# d150_in8_rev_a.net
KiCad netlist of a schematic drawn in EAGLE
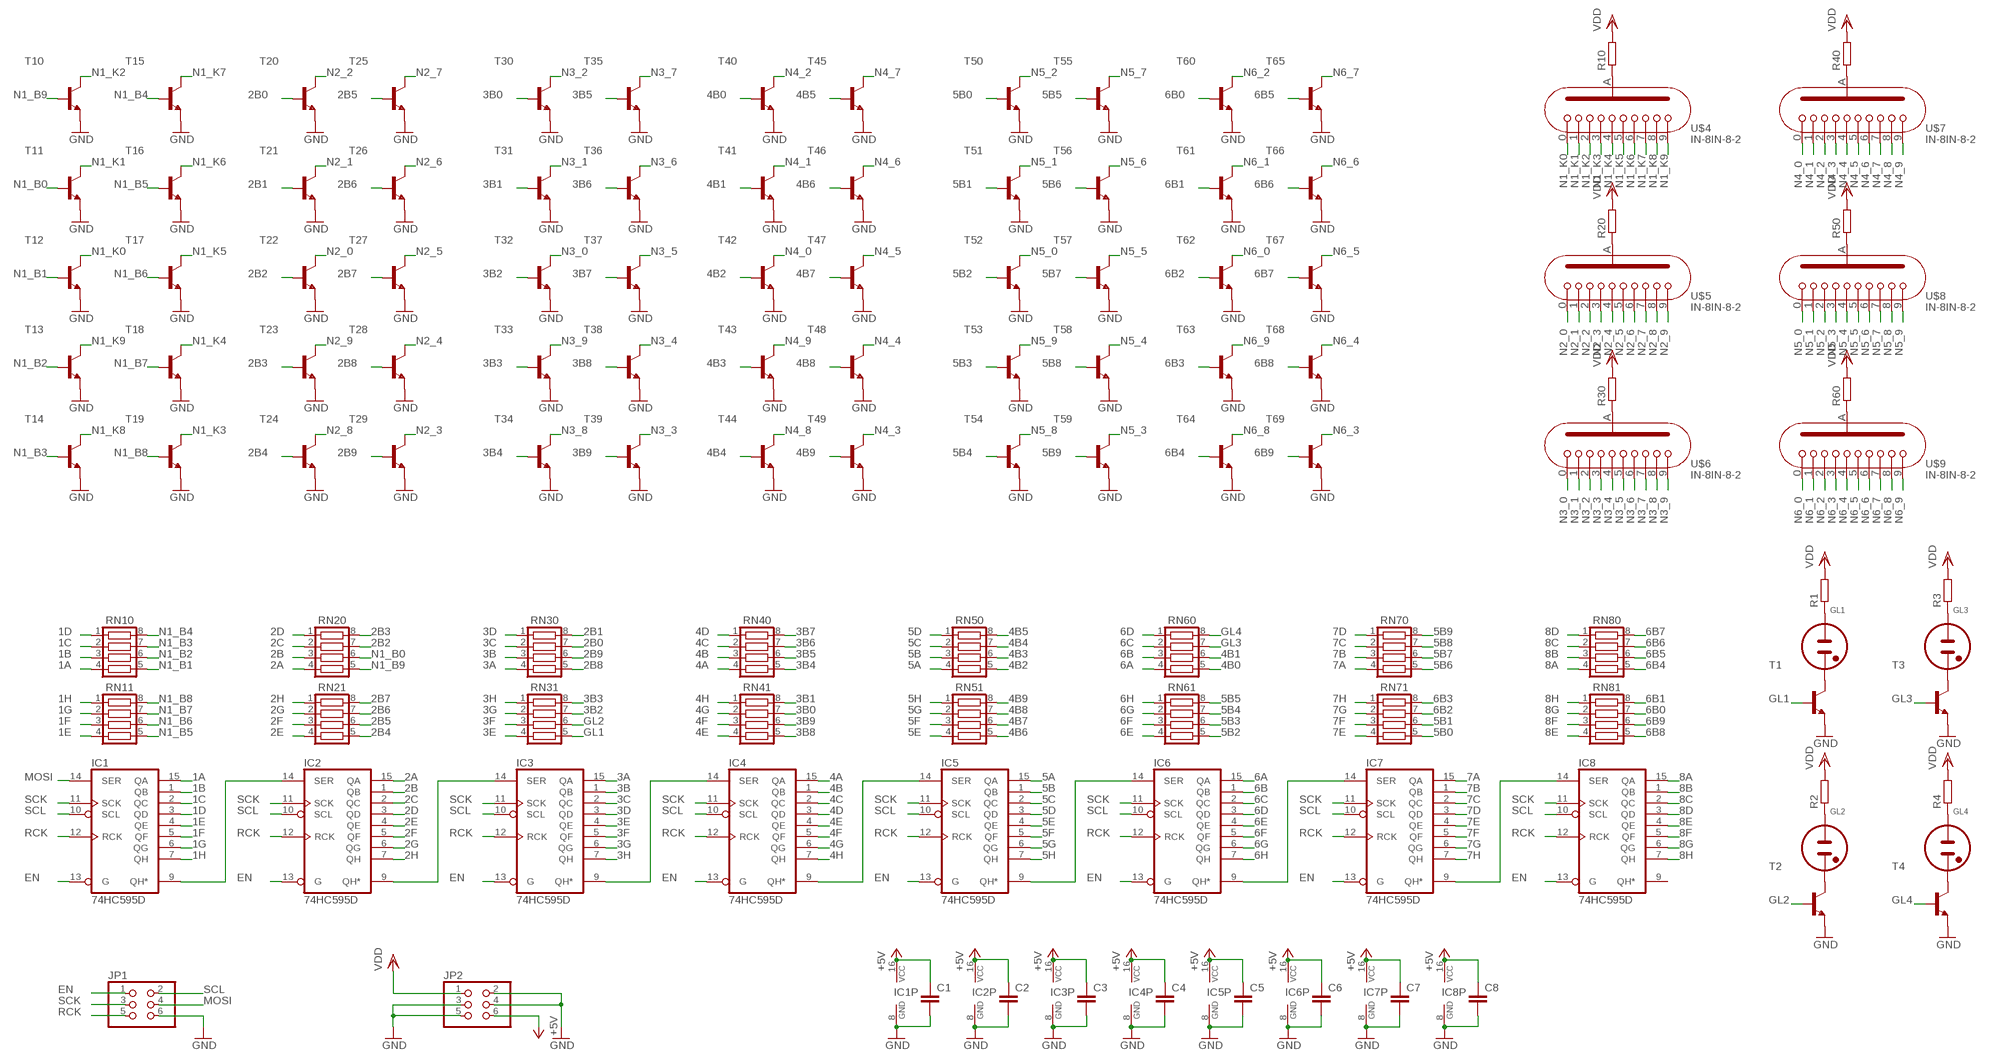
[diagram p0: schematic, sheet 1]

(export (version "E")
  (design (tool "Eeschema 10.0.6"))
  (components
    (comp (ref "C1")
      (value "C-EUC0603")
      (footprint "eagle-import:C0603")
      (libsource (lib "eagle-import") (part "C-EUC0603"))
    )
    (comp (ref "C2")
      (value "C-EUC0603")
      (footprint "eagle-import:C0603")
      (libsource (lib "eagle-import") (part "C-EUC0603"))
    )
    (comp (ref "C3")
      (value "C-EUC0603")
      (footprint "eagle-import:C0603")
      (libsource (lib "eagle-import") (part "C-EUC0603"))
    )
    (comp (ref "C4")
      (value "C-EUC0603")
      (footprint "eagle-import:C0603")
      (libsource (lib "eagle-import") (part "C-EUC0603"))
    )
    (comp (ref "C5")
      (value "C-EUC0603")
      (footprint "eagle-import:C0603")
      (libsource (lib "eagle-import") (part "C-EUC0603"))
    )
    (comp (ref "C6")
      (value "C-EUC0603")
      (footprint "eagle-import:C0603")
      (libsource (lib "eagle-import") (part "C-EUC0603"))
    )
    (comp (ref "C7")
      (value "C-EUC0603")
      (footprint "eagle-import:C0603")
      (libsource (lib "eagle-import") (part "C-EUC0603"))
    )
    (comp (ref "C8")
      (value "C-EUC0603")
      (footprint "eagle-import:C0603")
      (libsource (lib "eagle-import") (part "C-EUC0603"))
    )
    (comp (ref "GL1")
      (value "NE2-NEON-BULB-DRILL")
      (footprint "eagle-import:NE2-NEON-BULB-DRILL")
      (libsource (lib "eagle-import") (part "NE2-NEON-BULB-DRILL"))
    )
    (comp (ref "GL2")
      (value "NE2-NEON-BULB-DRILL")
      (footprint "eagle-import:NE2-NEON-BULB-DRILL")
      (libsource (lib "eagle-import") (part "NE2-NEON-BULB-DRILL"))
    )
    (comp (ref "GL3")
      (value "NE2-NEON-BULB-DRILL")
      (footprint "eagle-import:NE2-NEON-BULB-DRILL")
      (libsource (lib "eagle-import") (part "NE2-NEON-BULB-DRILL"))
    )
    (comp (ref "GL4")
      (value "NE2-NEON-BULB-DRILL")
      (footprint "eagle-import:NE2-NEON-BULB-DRILL")
      (libsource (lib "eagle-import") (part "NE2-NEON-BULB-DRILL"))
    )
    (comp (ref "IC1")
      (value "74HC595D")
      (footprint "eagle-import:SO16")
      (libsource (lib "eagle-import") (part "74595DHC"))
    )
    (comp (ref "IC2")
      (value "74HC595D")
      (footprint "eagle-import:SO16")
      (libsource (lib "eagle-import") (part "74595DHC"))
    )
    (comp (ref "IC3")
      (value "74HC595D")
      (footprint "eagle-import:SO16")
      (libsource (lib "eagle-import") (part "74595DHC"))
    )
    (comp (ref "IC4")
      (value "74HC595D")
      (footprint "eagle-import:SO16")
      (libsource (lib "eagle-import") (part "74595DHC"))
    )
    (comp (ref "IC5")
      (value "74HC595D")
      (footprint "eagle-import:SO16")
      (libsource (lib "eagle-import") (part "74595DHC"))
    )
    (comp (ref "IC6")
      (value "74HC595D")
      (footprint "eagle-import:SO16")
      (libsource (lib "eagle-import") (part "74595DHC"))
    )
    (comp (ref "IC7")
      (value "74HC595D")
      (footprint "eagle-import:SO16")
      (libsource (lib "eagle-import") (part "74595DHC"))
    )
    (comp (ref "IC8")
      (value "74HC595D")
      (footprint "eagle-import:SO16")
      (libsource (lib "eagle-import") (part "74595DHC"))
    )
    (comp (ref "JP1")
      (value "PINHD-2X3_2.54-SMD")
      (footprint "eagle-import:2X03SMD")
      (libsource (lib "eagle-import") (part "PINHD-2X3_2.54-SMD"))
    )
    (comp (ref "JP2")
      (value "PINHD-2X3_2.54-SMD")
      (footprint "eagle-import:2X03SMD")
      (libsource (lib "eagle-import") (part "PINHD-2X3_2.54-SMD"))
    )
    (comp (ref "R1")
      (value "R-EU_R0603")
      (footprint "eagle-import:R0603")
      (libsource (lib "eagle-import") (part "R-EU_R0603"))
    )
    (comp (ref "R2")
      (value "R-EU_R0603")
      (footprint "eagle-import:R0603")
      (libsource (lib "eagle-import") (part "R-EU_R0603"))
    )
    (comp (ref "R3")
      (value "R-EU_R0603")
      (footprint "eagle-import:R0603")
      (libsource (lib "eagle-import") (part "R-EU_R0603"))
    )
    (comp (ref "R4")
      (value "R-EU_R0603")
      (footprint "eagle-import:R0603")
      (libsource (lib "eagle-import") (part "R-EU_R0603"))
    )
    (comp (ref "R10")
      (value "R-EU_R0603")
      (footprint "eagle-import:R0603")
      (libsource (lib "eagle-import") (part "R-EU_R0603"))
    )
    (comp (ref "R20")
      (value "R-EU_R0603")
      (footprint "eagle-import:R0603")
      (libsource (lib "eagle-import") (part "R-EU_R0603"))
    )
    (comp (ref "R30")
      (value "R-EU_R0603")
      (footprint "eagle-import:R0603")
      (libsource (lib "eagle-import") (part "R-EU_R0603"))
    )
    (comp (ref "R40")
      (value "R-EU_R0603")
      (footprint "eagle-import:R0603")
      (libsource (lib "eagle-import") (part "R-EU_R0603"))
    )
    (comp (ref "R50")
      (value "R-EU_R0603")
      (footprint "eagle-import:R0603")
      (libsource (lib "eagle-import") (part "R-EU_R0603"))
    )
    (comp (ref "R60")
      (value "R-EU_R0603")
      (footprint "eagle-import:R0603")
      (libsource (lib "eagle-import") (part "R-EU_R0603"))
    )
    (comp (ref "RN10")
      (value "CTS742C083")
      (footprint "eagle-import:CTS742C083")
      (fields (field (name "OC_FARNELL") "unknown") (field (name "OC_NEWARK") "unknown"))
      (libsource (lib "eagle-import") (part "CTS742C083"))
    )
    (comp (ref "RN11")
      (value "CTS742C083")
      (footprint "eagle-import:CTS742C083")
      (fields (field (name "OC_FARNELL") "unknown") (field (name "OC_NEWARK") "unknown"))
      (libsource (lib "eagle-import") (part "CTS742C083"))
    )
    (comp (ref "RN20")
      (value "CTS742C083")
      (footprint "eagle-import:CTS742C083")
      (fields (field (name "OC_FARNELL") "unknown") (field (name "OC_NEWARK") "unknown"))
      (libsource (lib "eagle-import") (part "CTS742C083"))
    )
    (comp (ref "RN21")
      (value "CTS742C083")
      (footprint "eagle-import:CTS742C083")
      (fields (field (name "OC_FARNELL") "unknown") (field (name "OC_NEWARK") "unknown"))
      (libsource (lib "eagle-import") (part "CTS742C083"))
    )
    (comp (ref "RN30")
      (value "CTS742C083")
      (footprint "eagle-import:CTS742C083")
      (fields (field (name "OC_FARNELL") "unknown") (field (name "OC_NEWARK") "unknown"))
      (libsource (lib "eagle-import") (part "CTS742C083"))
    )
    (comp (ref "RN31")
      (value "CTS742C083")
      (footprint "eagle-import:CTS742C083")
      (fields (field (name "OC_FARNELL") "unknown") (field (name "OC_NEWARK") "unknown"))
      (libsource (lib "eagle-import") (part "CTS742C083"))
    )
    (comp (ref "RN40")
      (value "CTS742C083")
      (footprint "eagle-import:CTS742C083")
      (fields (field (name "OC_FARNELL") "unknown") (field (name "OC_NEWARK") "unknown"))
      (libsource (lib "eagle-import") (part "CTS742C083"))
    )
    (comp (ref "RN41")
      (value "CTS742C083")
      (footprint "eagle-import:CTS742C083")
      (fields (field (name "OC_FARNELL") "unknown") (field (name "OC_NEWARK") "unknown"))
      (libsource (lib "eagle-import") (part "CTS742C083"))
    )
    (comp (ref "RN50")
      (value "CTS742C083")
      (footprint "eagle-import:CTS742C083")
      (fields (field (name "OC_FARNELL") "unknown") (field (name "OC_NEWARK") "unknown"))
      (libsource (lib "eagle-import") (part "CTS742C083"))
    )
    (comp (ref "RN51")
      (value "CTS742C083")
      (footprint "eagle-import:CTS742C083")
      (fields (field (name "OC_FARNELL") "unknown") (field (name "OC_NEWARK") "unknown"))
      (libsource (lib "eagle-import") (part "CTS742C083"))
    )
    (comp (ref "RN60")
      (value "CTS742C083")
      (footprint "eagle-import:CTS742C083")
      (fields (field (name "OC_FARNELL") "unknown") (field (name "OC_NEWARK") "unknown"))
      (libsource (lib "eagle-import") (part "CTS742C083"))
    )
    (comp (ref "RN61")
      (value "CTS742C083")
      (footprint "eagle-import:CTS742C083")
      (fields (field (name "OC_FARNELL") "unknown") (field (name "OC_NEWARK") "unknown"))
      (libsource (lib "eagle-import") (part "CTS742C083"))
    )
    (comp (ref "RN70")
      (value "CTS742C083")
      (footprint "eagle-import:CTS742C083")
      (fields (field (name "OC_FARNELL") "unknown") (field (name "OC_NEWARK") "unknown"))
      (libsource (lib "eagle-import") (part "CTS742C083"))
    )
    (comp (ref "RN71")
      (value "CTS742C083")
      (footprint "eagle-import:CTS742C083")
      (fields (field (name "OC_FARNELL") "unknown") (field (name "OC_NEWARK") "unknown"))
      (libsource (lib "eagle-import") (part "CTS742C083"))
    )
    (comp (ref "RN80")
      (value "CTS742C083")
      (footprint "eagle-import:CTS742C083")
      (fields (field (name "OC_FARNELL") "unknown") (field (name "OC_NEWARK") "unknown"))
      (libsource (lib "eagle-import") (part "CTS742C083"))
    )
    (comp (ref "RN81")
      (value "CTS742C083")
      (footprint "eagle-import:CTS742C083")
      (fields (field (name "OC_FARNELL") "unknown") (field (name "OC_NEWARK") "unknown"))
      (libsource (lib "eagle-import") (part "CTS742C083"))
    )
    (comp (ref "T1")
      (value "SMBTA42")
      (footprint "eagle-import:SOT23")
      (libsource (lib "eagle-import") (part "SMBTA42"))
    )
    (comp (ref "T2")
      (value "SMBTA42")
      (footprint "eagle-import:SOT23")
      (libsource (lib "eagle-import") (part "SMBTA42"))
    )
    (comp (ref "T3")
      (value "SMBTA42")
      (footprint "eagle-import:SOT23")
      (libsource (lib "eagle-import") (part "SMBTA42"))
    )
    (comp (ref "T4")
      (value "SMBTA42")
      (footprint "eagle-import:SOT23")
      (libsource (lib "eagle-import") (part "SMBTA42"))
    )
    (comp (ref "T10")
      (value "SMBTA42")
      (footprint "eagle-import:SOT23")
      (libsource (lib "eagle-import") (part "SMBTA42"))
    )
    (comp (ref "T11")
      (value "SMBTA42")
      (footprint "eagle-import:SOT23")
      (libsource (lib "eagle-import") (part "SMBTA42"))
    )
    (comp (ref "T12")
      (value "SMBTA42")
      (footprint "eagle-import:SOT23")
      (libsource (lib "eagle-import") (part "SMBTA42"))
    )
    (comp (ref "T13")
      (value "SMBTA42")
      (footprint "eagle-import:SOT23")
      (libsource (lib "eagle-import") (part "SMBTA42"))
    )
    (comp (ref "T14")
      (value "SMBTA42")
      (footprint "eagle-import:SOT23")
      (libsource (lib "eagle-import") (part "SMBTA42"))
    )
    (comp (ref "T15")
      (value "SMBTA42")
      (footprint "eagle-import:SOT23")
      (libsource (lib "eagle-import") (part "SMBTA42"))
    )
    (comp (ref "T16")
      (value "SMBTA42")
      (footprint "eagle-import:SOT23")
      (libsource (lib "eagle-import") (part "SMBTA42"))
    )
    (comp (ref "T17")
      (value "SMBTA42")
      (footprint "eagle-import:SOT23")
      (libsource (lib "eagle-import") (part "SMBTA42"))
    )
    (comp (ref "T18")
      (value "SMBTA42")
      (footprint "eagle-import:SOT23")
      (libsource (lib "eagle-import") (part "SMBTA42"))
    )
    (comp (ref "T19")
      (value "SMBTA42")
      (footprint "eagle-import:SOT23")
      (libsource (lib "eagle-import") (part "SMBTA42"))
    )
    (comp (ref "T20")
      (value "SMBTA42")
      (footprint "eagle-import:SOT23")
      (libsource (lib "eagle-import") (part "SMBTA42"))
    )
    (comp (ref "T21")
      (value "SMBTA42")
      (footprint "eagle-import:SOT23")
      (libsource (lib "eagle-import") (part "SMBTA42"))
    )
    (comp (ref "T22")
      (value "SMBTA42")
      (footprint "eagle-import:SOT23")
      (libsource (lib "eagle-import") (part "SMBTA42"))
    )
    (comp (ref "T23")
      (value "SMBTA42")
      (footprint "eagle-import:SOT23")
      (libsource (lib "eagle-import") (part "SMBTA42"))
    )
    (comp (ref "T24")
      (value "SMBTA42")
      (footprint "eagle-import:SOT23")
      (libsource (lib "eagle-import") (part "SMBTA42"))
    )
    (comp (ref "T25")
      (value "SMBTA42")
      (footprint "eagle-import:SOT23")
      (libsource (lib "eagle-import") (part "SMBTA42"))
    )
    (comp (ref "T26")
      (value "SMBTA42")
      (footprint "eagle-import:SOT23")
      (libsource (lib "eagle-import") (part "SMBTA42"))
    )
    (comp (ref "T27")
      (value "SMBTA42")
      (footprint "eagle-import:SOT23")
      (libsource (lib "eagle-import") (part "SMBTA42"))
    )
    (comp (ref "T28")
      (value "SMBTA42")
      (footprint "eagle-import:SOT23")
      (libsource (lib "eagle-import") (part "SMBTA42"))
    )
    (comp (ref "T29")
      (value "SMBTA42")
      (footprint "eagle-import:SOT23")
      (libsource (lib "eagle-import") (part "SMBTA42"))
    )
    (comp (ref "T30")
      (value "SMBTA42")
      (footprint "eagle-import:SOT23")
      (libsource (lib "eagle-import") (part "SMBTA42"))
    )
    (comp (ref "T31")
      (value "SMBTA42")
      (footprint "eagle-import:SOT23")
      (libsource (lib "eagle-import") (part "SMBTA42"))
    )
    (comp (ref "T32")
      (value "SMBTA42")
      (footprint "eagle-import:SOT23")
      (libsource (lib "eagle-import") (part "SMBTA42"))
    )
    (comp (ref "T33")
      (value "SMBTA42")
      (footprint "eagle-import:SOT23")
      (libsource (lib "eagle-import") (part "SMBTA42"))
    )
    (comp (ref "T34")
      (value "SMBTA42")
      (footprint "eagle-import:SOT23")
      (libsource (lib "eagle-import") (part "SMBTA42"))
    )
    (comp (ref "T35")
      (value "SMBTA42")
      (footprint "eagle-import:SOT23")
      (libsource (lib "eagle-import") (part "SMBTA42"))
    )
    (comp (ref "T36")
      (value "SMBTA42")
      (footprint "eagle-import:SOT23")
      (libsource (lib "eagle-import") (part "SMBTA42"))
    )
    (comp (ref "T37")
      (value "SMBTA42")
      (footprint "eagle-import:SOT23")
      (libsource (lib "eagle-import") (part "SMBTA42"))
    )
    (comp (ref "T38")
      (value "SMBTA42")
      (footprint "eagle-import:SOT23")
      (libsource (lib "eagle-import") (part "SMBTA42"))
    )
    (comp (ref "T39")
      (value "SMBTA42")
      (footprint "eagle-import:SOT23")
      (libsource (lib "eagle-import") (part "SMBTA42"))
    )
    (comp (ref "T40")
      (value "SMBTA42")
      (footprint "eagle-import:SOT23")
      (libsource (lib "eagle-import") (part "SMBTA42"))
    )
    (comp (ref "T41")
      (value "SMBTA42")
      (footprint "eagle-import:SOT23")
      (libsource (lib "eagle-import") (part "SMBTA42"))
    )
    (comp (ref "T42")
      (value "SMBTA42")
      (footprint "eagle-import:SOT23")
      (libsource (lib "eagle-import") (part "SMBTA42"))
    )
    (comp (ref "T43")
      (value "SMBTA42")
      (footprint "eagle-import:SOT23")
      (libsource (lib "eagle-import") (part "SMBTA42"))
    )
    (comp (ref "T44")
      (value "SMBTA42")
      (footprint "eagle-import:SOT23")
      (libsource (lib "eagle-import") (part "SMBTA42"))
    )
    (comp (ref "T45")
      (value "SMBTA42")
      (footprint "eagle-import:SOT23")
      (libsource (lib "eagle-import") (part "SMBTA42"))
    )
    (comp (ref "T46")
      (value "SMBTA42")
      (footprint "eagle-import:SOT23")
      (libsource (lib "eagle-import") (part "SMBTA42"))
    )
    (comp (ref "T47")
      (value "SMBTA42")
      (footprint "eagle-import:SOT23")
      (libsource (lib "eagle-import") (part "SMBTA42"))
    )
    (comp (ref "T48")
      (value "SMBTA42")
      (footprint "eagle-import:SOT23")
      (libsource (lib "eagle-import") (part "SMBTA42"))
    )
    (comp (ref "T49")
      (value "SMBTA42")
      (footprint "eagle-import:SOT23")
      (libsource (lib "eagle-import") (part "SMBTA42"))
    )
    (comp (ref "T50")
      (value "SMBTA42")
      (footprint "eagle-import:SOT23")
      (libsource (lib "eagle-import") (part "SMBTA42"))
    )
    (comp (ref "T51")
      (value "SMBTA42")
      (footprint "eagle-import:SOT23")
      (libsource (lib "eagle-import") (part "SMBTA42"))
    )
    (comp (ref "T52")
      (value "SMBTA42")
      (footprint "eagle-import:SOT23")
      (libsource (lib "eagle-import") (part "SMBTA42"))
    )
    (comp (ref "T53")
      (value "SMBTA42")
      (footprint "eagle-import:SOT23")
      (libsource (lib "eagle-import") (part "SMBTA42"))
    )
    (comp (ref "T54")
      (value "SMBTA42")
      (footprint "eagle-import:SOT23")
      (libsource (lib "eagle-import") (part "SMBTA42"))
    )
    (comp (ref "T55")
      (value "SMBTA42")
      (footprint "eagle-import:SOT23")
      (libsource (lib "eagle-import") (part "SMBTA42"))
    )
    (comp (ref "T56")
      (value "SMBTA42")
      (footprint "eagle-import:SOT23")
      (libsource (lib "eagle-import") (part "SMBTA42"))
    )
    (comp (ref "T57")
      (value "SMBTA42")
      (footprint "eagle-import:SOT23")
      (libsource (lib "eagle-import") (part "SMBTA42"))
    )
    (comp (ref "T58")
      (value "SMBTA42")
      (footprint "eagle-import:SOT23")
      (libsource (lib "eagle-import") (part "SMBTA42"))
    )
    (comp (ref "T59")
      (value "SMBTA42")
      (footprint "eagle-import:SOT23")
      (libsource (lib "eagle-import") (part "SMBTA42"))
    )
    (comp (ref "T60")
      (value "SMBTA42")
      (footprint "eagle-import:SOT23")
      (libsource (lib "eagle-import") (part "SMBTA42"))
    )
    (comp (ref "T61")
      (value "SMBTA42")
      (footprint "eagle-import:SOT23")
      (libsource (lib "eagle-import") (part "SMBTA42"))
    )
    (comp (ref "T62")
      (value "SMBTA42")
      (footprint "eagle-import:SOT23")
      (libsource (lib "eagle-import") (part "SMBTA42"))
    )
    (comp (ref "T63")
      (value "SMBTA42")
      (footprint "eagle-import:SOT23")
      (libsource (lib "eagle-import") (part "SMBTA42"))
    )
    (comp (ref "T64")
      (value "SMBTA42")
      (footprint "eagle-import:SOT23")
      (libsource (lib "eagle-import") (part "SMBTA42"))
    )
    (comp (ref "T65")
      (value "SMBTA42")
      (footprint "eagle-import:SOT23")
      (libsource (lib "eagle-import") (part "SMBTA42"))
    )
    (comp (ref "T66")
      (value "SMBTA42")
      (footprint "eagle-import:SOT23")
      (libsource (lib "eagle-import") (part "SMBTA42"))
    )
    (comp (ref "T67")
      (value "SMBTA42")
      (footprint "eagle-import:SOT23")
      (libsource (lib "eagle-import") (part "SMBTA42"))
    )
    (comp (ref "T68")
      (value "SMBTA42")
      (footprint "eagle-import:SOT23")
      (libsource (lib "eagle-import") (part "SMBTA42"))
    )
    (comp (ref "T69")
      (value "SMBTA42")
      (footprint "eagle-import:SOT23")
      (libsource (lib "eagle-import") (part "SMBTA42"))
    )
    (comp (ref "U$4")
      (value "IN-8IN-8-2")
      (footprint "eagle-import:IN-8-2")
      (libsource (lib "eagle-import") (part "IN-8IN-8-2"))
    )
    (comp (ref "U$5")
      (value "IN-8IN-8-2")
      (footprint "eagle-import:IN-8-2")
      (libsource (lib "eagle-import") (part "IN-8IN-8-2"))
    )
    (comp (ref "U$6")
      (value "IN-8IN-8-2")
      (footprint "eagle-import:IN-8-2")
      (libsource (lib "eagle-import") (part "IN-8IN-8-2"))
    )
    (comp (ref "U$7")
      (value "IN-8IN-8-2")
      (footprint "eagle-import:IN-8-2")
      (libsource (lib "eagle-import") (part "IN-8IN-8-2"))
    )
    (comp (ref "U$8")
      (value "IN-8IN-8-2")
      (footprint "eagle-import:IN-8-2")
      (libsource (lib "eagle-import") (part "IN-8IN-8-2"))
    )
    (comp (ref "U$9")
      (value "IN-8IN-8-2")
      (footprint "eagle-import:IN-8-2")
      (libsource (lib "eagle-import") (part "IN-8IN-8-2"))
    )
  )
  (nets
    (net (code "1") (name "+5V") (class "Default")
      (node (ref "C1") (pin "1") (pinfunction "1_1") (pintype "passive"))
      (node (ref "C2") (pin "1") (pinfunction "1_1") (pintype "passive"))
      (node (ref "C3") (pin "1") (pinfunction "1_1") (pintype "passive"))
      (node (ref "C4") (pin "1") (pinfunction "1_1") (pintype "passive"))
      (node (ref "C5") (pin "1") (pinfunction "1_1") (pintype "passive"))
      (node (ref "C6") (pin "1") (pinfunction "1_1") (pintype "passive"))
      (node (ref "C7") (pin "1") (pinfunction "1_1") (pintype "passive"))
      (node (ref "C8") (pin "1") (pinfunction "1_1") (pintype "passive"))
      (node (ref "IC1") (pin "16") (pinfunction "VCC_16") (pintype "power_in"))
      (node (ref "IC2") (pin "16") (pinfunction "VCC_16") (pintype "power_in"))
      (node (ref "IC3") (pin "16") (pinfunction "VCC_16") (pintype "power_in"))
      (node (ref "IC4") (pin "16") (pinfunction "VCC_16") (pintype "power_in"))
      (node (ref "IC5") (pin "16") (pinfunction "VCC_16") (pintype "power_in"))
      (node (ref "IC6") (pin "16") (pinfunction "VCC_16") (pintype "power_in"))
      (node (ref "IC7") (pin "16") (pinfunction "VCC_16") (pintype "power_in"))
      (node (ref "IC8") (pin "16") (pinfunction "VCC_16") (pintype "power_in"))
      (node (ref "JP2") (pin "6") (pinfunction "6_6") (pintype "passive"))
    )
    (net (code "2") (name "/1A") (class "Default")
      (node (ref "IC1") (pin "15") (pinfunction "QA_15") (pintype "tri_state"))
      (node (ref "RN10") (pin "4") (pinfunction "4_4") (pintype "passive"))
    )
    (net (code "3") (name "/1B") (class "Default")
      (node (ref "IC1") (pin "1") (pinfunction "QB_1") (pintype "tri_state"))
      (node (ref "RN10") (pin "3") (pinfunction "3_3") (pintype "passive"))
    )
    (net (code "4") (name "/1C") (class "Default")
      (node (ref "IC1") (pin "2") (pinfunction "QC_2") (pintype "tri_state"))
      (node (ref "RN10") (pin "2") (pinfunction "2_2") (pintype "passive"))
    )
    (net (code "5") (name "/1D") (class "Default")
      (node (ref "IC1") (pin "3") (pinfunction "QD_3") (pintype "tri_state"))
      (node (ref "RN10") (pin "1") (pinfunction "1_1") (pintype "passive"))
    )
    (net (code "6") (name "/1E") (class "Default")
      (node (ref "IC1") (pin "4") (pinfunction "QE_4") (pintype "tri_state"))
      (node (ref "RN11") (pin "4") (pinfunction "4_4") (pintype "passive"))
    )
    (net (code "7") (name "/1F") (class "Default")
      (node (ref "IC1") (pin "5") (pinfunction "QF_5") (pintype "tri_state"))
      (node (ref "RN11") (pin "3") (pinfunction "3_3") (pintype "passive"))
    )
    (net (code "8") (name "/1G") (class "Default")
      (node (ref "IC1") (pin "6") (pinfunction "QG_6") (pintype "tri_state"))
      (node (ref "RN11") (pin "2") (pinfunction "2_2") (pintype "passive"))
    )
    (net (code "9") (name "/1H") (class "Default")
      (node (ref "IC1") (pin "7") (pinfunction "QH_7") (pintype "tri_state"))
      (node (ref "RN11") (pin "1") (pinfunction "1_1") (pintype "passive"))
    )
    (net (code "10") (name "/2A") (class "Default")
      (node (ref "IC2") (pin "15") (pinfunction "QA_15") (pintype "tri_state"))
      (node (ref "RN20") (pin "4") (pinfunction "4_4") (pintype "passive"))
    )
    (net (code "11") (name "/2B") (class "Default")
      (node (ref "IC2") (pin "1") (pinfunction "QB_1") (pintype "tri_state"))
      (node (ref "RN20") (pin "3") (pinfunction "3_3") (pintype "passive"))
    )
    (net (code "12") (name "/2B0") (class "Default")
      (node (ref "RN30") (pin "7") (pinfunction "7_7") (pintype "passive"))
      (node (ref "T20") (pin "1") (pinfunction "B_1") (pintype "passive"))
    )
    (net (code "13") (name "/2B1") (class "Default")
      (node (ref "RN30") (pin "8") (pinfunction "8_8") (pintype "passive"))
      (node (ref "T21") (pin "1") (pinfunction "B_1") (pintype "passive"))
    )
    (net (code "14") (name "/2B2") (class "Default")
      (node (ref "RN20") (pin "7") (pinfunction "7_7") (pintype "passive"))
      (node (ref "T22") (pin "1") (pinfunction "B_1") (pintype "passive"))
    )
    (net (code "15") (name "/2B3") (class "Default")
      (node (ref "RN20") (pin "8") (pinfunction "8_8") (pintype "passive"))
      (node (ref "T23") (pin "1") (pinfunction "B_1") (pintype "passive"))
    )
    (net (code "16") (name "/2B4") (class "Default")
      (node (ref "RN21") (pin "5") (pinfunction "5_5") (pintype "passive"))
      (node (ref "T24") (pin "1") (pinfunction "B_1") (pintype "passive"))
    )
    (net (code "17") (name "/2B5") (class "Default")
      (node (ref "RN21") (pin "6") (pinfunction "6_6") (pintype "passive"))
      (node (ref "T25") (pin "1") (pinfunction "B_1") (pintype "passive"))
    )
    (net (code "18") (name "/2B6") (class "Default")
      (node (ref "RN21") (pin "7") (pinfunction "7_7") (pintype "passive"))
      (node (ref "T26") (pin "1") (pinfunction "B_1") (pintype "passive"))
    )
    (net (code "19") (name "/2B7") (class "Default")
      (node (ref "RN21") (pin "8") (pinfunction "8_8") (pintype "passive"))
      (node (ref "T27") (pin "1") (pinfunction "B_1") (pintype "passive"))
    )
    (net (code "20") (name "/2B8") (class "Default")
      (node (ref "RN30") (pin "5") (pinfunction "5_5") (pintype "passive"))
      (node (ref "T28") (pin "1") (pinfunction "B_1") (pintype "passive"))
    )
    (net (code "21") (name "/2B9") (class "Default")
      (node (ref "RN30") (pin "6") (pinfunction "6_6") (pintype "passive"))
      (node (ref "T29") (pin "1") (pinfunction "B_1") (pintype "passive"))
    )
    (net (code "22") (name "/2C") (class "Default")
      (node (ref "IC2") (pin "2") (pinfunction "QC_2") (pintype "tri_state"))
      (node (ref "RN20") (pin "2") (pinfunction "2_2") (pintype "passive"))
    )
    (net (code "23") (name "/2D") (class "Default")
      (node (ref "IC2") (pin "3") (pinfunction "QD_3") (pintype "tri_state"))
      (node (ref "RN20") (pin "1") (pinfunction "1_1") (pintype "passive"))
    )
    (net (code "24") (name "/2E") (class "Default")
      (node (ref "IC2") (pin "4") (pinfunction "QE_4") (pintype "tri_state"))
      (node (ref "RN21") (pin "4") (pinfunction "4_4") (pintype "passive"))
    )
    (net (code "25") (name "/2F") (class "Default")
      (node (ref "IC2") (pin "5") (pinfunction "QF_5") (pintype "tri_state"))
      (node (ref "RN21") (pin "3") (pinfunction "3_3") (pintype "passive"))
    )
    (net (code "26") (name "/2G") (class "Default")
      (node (ref "IC2") (pin "6") (pinfunction "QG_6") (pintype "tri_state"))
      (node (ref "RN21") (pin "2") (pinfunction "2_2") (pintype "passive"))
    )
    (net (code "27") (name "/2H") (class "Default")
      (node (ref "IC2") (pin "7") (pinfunction "QH_7") (pintype "tri_state"))
      (node (ref "RN21") (pin "1") (pinfunction "1_1") (pintype "passive"))
    )
    (net (code "28") (name "/3A") (class "Default")
      (node (ref "IC3") (pin "15") (pinfunction "QA_15") (pintype "tri_state"))
      (node (ref "RN30") (pin "4") (pinfunction "4_4") (pintype "passive"))
    )
    (net (code "29") (name "/3B") (class "Default")
      (node (ref "IC3") (pin "1") (pinfunction "QB_1") (pintype "tri_state"))
      (node (ref "RN30") (pin "3") (pinfunction "3_3") (pintype "passive"))
    )
    (net (code "30") (name "/3B0") (class "Default")
      (node (ref "RN41") (pin "7") (pinfunction "7_7") (pintype "passive"))
      (node (ref "T30") (pin "1") (pinfunction "B_1") (pintype "passive"))
    )
    (net (code "31") (name "/3B1") (class "Default")
      (node (ref "RN41") (pin "8") (pinfunction "8_8") (pintype "passive"))
      (node (ref "T31") (pin "1") (pinfunction "B_1") (pintype "passive"))
    )
    (net (code "32") (name "/3B2") (class "Default")
      (node (ref "RN31") (pin "7") (pinfunction "7_7") (pintype "passive"))
      (node (ref "T32") (pin "1") (pinfunction "B_1") (pintype "passive"))
    )
    (net (code "33") (name "/3B3") (class "Default")
      (node (ref "RN31") (pin "8") (pinfunction "8_8") (pintype "passive"))
      (node (ref "T33") (pin "1") (pinfunction "B_1") (pintype "passive"))
    )
    (net (code "34") (name "/3B4") (class "Default")
      (node (ref "RN40") (pin "5") (pinfunction "5_5") (pintype "passive"))
      (node (ref "T34") (pin "1") (pinfunction "B_1") (pintype "passive"))
    )
    (net (code "35") (name "/3B5") (class "Default")
      (node (ref "RN40") (pin "6") (pinfunction "6_6") (pintype "passive"))
      (node (ref "T35") (pin "1") (pinfunction "B_1") (pintype "passive"))
    )
    (net (code "36") (name "/3B6") (class "Default")
      (node (ref "RN40") (pin "7") (pinfunction "7_7") (pintype "passive"))
      (node (ref "T36") (pin "1") (pinfunction "B_1") (pintype "passive"))
    )
    (net (code "37") (name "/3B7") (class "Default")
      (node (ref "RN40") (pin "8") (pinfunction "8_8") (pintype "passive"))
      (node (ref "T37") (pin "1") (pinfunction "B_1") (pintype "passive"))
    )
    (net (code "38") (name "/3B8") (class "Default")
      (node (ref "RN41") (pin "5") (pinfunction "5_5") (pintype "passive"))
      (node (ref "T38") (pin "1") (pinfunction "B_1") (pintype "passive"))
    )
    (net (code "39") (name "/3B9") (class "Default")
      (node (ref "RN41") (pin "6") (pinfunction "6_6") (pintype "passive"))
      (node (ref "T39") (pin "1") (pinfunction "B_1") (pintype "passive"))
    )
    (net (code "40") (name "/3C") (class "Default")
      (node (ref "IC3") (pin "2") (pinfunction "QC_2") (pintype "tri_state"))
      (node (ref "RN30") (pin "2") (pinfunction "2_2") (pintype "passive"))
    )
    (net (code "41") (name "/3D") (class "Default")
      (node (ref "IC3") (pin "3") (pinfunction "QD_3") (pintype "tri_state"))
      (node (ref "RN30") (pin "1") (pinfunction "1_1") (pintype "passive"))
    )
    (net (code "42") (name "/3E") (class "Default")
      (node (ref "IC3") (pin "4") (pinfunction "QE_4") (pintype "tri_state"))
      (node (ref "RN31") (pin "4") (pinfunction "4_4") (pintype "passive"))
    )
    (net (code "43") (name "/3F") (class "Default")
      (node (ref "IC3") (pin "5") (pinfunction "QF_5") (pintype "tri_state"))
      (node (ref "RN31") (pin "3") (pinfunction "3_3") (pintype "passive"))
    )
    (net (code "44") (name "/3G") (class "Default")
      (node (ref "IC3") (pin "6") (pinfunction "QG_6") (pintype "tri_state"))
      (node (ref "RN31") (pin "2") (pinfunction "2_2") (pintype "passive"))
    )
    (net (code "45") (name "/3H") (class "Default")
      (node (ref "IC3") (pin "7") (pinfunction "QH_7") (pintype "tri_state"))
      (node (ref "RN31") (pin "1") (pinfunction "1_1") (pintype "passive"))
    )
    (net (code "46") (name "/4A") (class "Default")
      (node (ref "IC4") (pin "15") (pinfunction "QA_15") (pintype "tri_state"))
      (node (ref "RN40") (pin "4") (pinfunction "4_4") (pintype "passive"))
    )
    (net (code "47") (name "/4B") (class "Default")
      (node (ref "IC4") (pin "1") (pinfunction "QB_1") (pintype "tri_state"))
      (node (ref "RN40") (pin "3") (pinfunction "3_3") (pintype "passive"))
    )
    (net (code "48") (name "/4B0") (class "Default")
      (node (ref "RN60") (pin "5") (pinfunction "5_5") (pintype "passive"))
      (node (ref "T40") (pin "1") (pinfunction "B_1") (pintype "passive"))
    )
    (net (code "49") (name "/4B1") (class "Default")
      (node (ref "RN60") (pin "6") (pinfunction "6_6") (pintype "passive"))
      (node (ref "T41") (pin "1") (pinfunction "B_1") (pintype "passive"))
    )
    (net (code "50") (name "/4B2") (class "Default")
      (node (ref "RN50") (pin "5") (pinfunction "5_5") (pintype "passive"))
      (node (ref "T42") (pin "1") (pinfunction "B_1") (pintype "passive"))
    )
    (net (code "51") (name "/4B3") (class "Default")
      (node (ref "RN50") (pin "6") (pinfunction "6_6") (pintype "passive"))
      (node (ref "T43") (pin "1") (pinfunction "B_1") (pintype "passive"))
    )
    (net (code "52") (name "/4B4") (class "Default")
      (node (ref "RN50") (pin "7") (pinfunction "7_7") (pintype "passive"))
      (node (ref "T44") (pin "1") (pinfunction "B_1") (pintype "passive"))
    )
    (net (code "53") (name "/4B5") (class "Default")
      (node (ref "RN50") (pin "8") (pinfunction "8_8") (pintype "passive"))
      (node (ref "T45") (pin "1") (pinfunction "B_1") (pintype "passive"))
    )
    (net (code "54") (name "/4B6") (class "Default")
      (node (ref "RN51") (pin "5") (pinfunction "5_5") (pintype "passive"))
      (node (ref "T46") (pin "1") (pinfunction "B_1") (pintype "passive"))
    )
    (net (code "55") (name "/4B7") (class "Default")
      (node (ref "RN51") (pin "6") (pinfunction "6_6") (pintype "passive"))
      (node (ref "T47") (pin "1") (pinfunction "B_1") (pintype "passive"))
    )
    (net (code "56") (name "/4B8") (class "Default")
      (node (ref "RN51") (pin "7") (pinfunction "7_7") (pintype "passive"))
      (node (ref "T48") (pin "1") (pinfunction "B_1") (pintype "passive"))
    )
    (net (code "57") (name "/4B9") (class "Default")
      (node (ref "RN51") (pin "8") (pinfunction "8_8") (pintype "passive"))
      (node (ref "T49") (pin "1") (pinfunction "B_1") (pintype "passive"))
    )
    (net (code "58") (name "/4C") (class "Default")
      (node (ref "IC4") (pin "2") (pinfunction "QC_2") (pintype "tri_state"))
      (node (ref "RN40") (pin "2") (pinfunction "2_2") (pintype "passive"))
    )
    (net (code "59") (name "/4D") (class "Default")
      (node (ref "IC4") (pin "3") (pinfunction "QD_3") (pintype "tri_state"))
      (node (ref "RN40") (pin "1") (pinfunction "1_1") (pintype "passive"))
    )
    (net (code "60") (name "/4E") (class "Default")
      (node (ref "IC4") (pin "4") (pinfunction "QE_4") (pintype "tri_state"))
      (node (ref "RN41") (pin "4") (pinfunction "4_4") (pintype "passive"))
    )
    (net (code "61") (name "/4F") (class "Default")
      (node (ref "IC4") (pin "5") (pinfunction "QF_5") (pintype "tri_state"))
      (node (ref "RN41") (pin "3") (pinfunction "3_3") (pintype "passive"))
    )
    (net (code "62") (name "/4G") (class "Default")
      (node (ref "IC4") (pin "6") (pinfunction "QG_6") (pintype "tri_state"))
      (node (ref "RN41") (pin "2") (pinfunction "2_2") (pintype "passive"))
    )
    (net (code "63") (name "/4H") (class "Default")
      (node (ref "IC4") (pin "7") (pinfunction "QH_7") (pintype "tri_state"))
      (node (ref "RN41") (pin "1") (pinfunction "1_1") (pintype "passive"))
    )
    (net (code "64") (name "/5A") (class "Default")
      (node (ref "IC5") (pin "15") (pinfunction "QA_15") (pintype "tri_state"))
      (node (ref "RN50") (pin "4") (pinfunction "4_4") (pintype "passive"))
    )
    (net (code "65") (name "/5B") (class "Default")
      (node (ref "IC5") (pin "1") (pinfunction "QB_1") (pintype "tri_state"))
      (node (ref "RN50") (pin "3") (pinfunction "3_3") (pintype "passive"))
    )
    (net (code "66") (name "/5B0") (class "Default")
      (node (ref "RN71") (pin "5") (pinfunction "5_5") (pintype "passive"))
      (node (ref "T50") (pin "1") (pinfunction "B_1") (pintype "passive"))
    )
    (net (code "67") (name "/5B1") (class "Default")
      (node (ref "RN71") (pin "6") (pinfunction "6_6") (pintype "passive"))
      (node (ref "T51") (pin "1") (pinfunction "B_1") (pintype "passive"))
    )
    (net (code "68") (name "/5B2") (class "Default")
      (node (ref "RN61") (pin "5") (pinfunction "5_5") (pintype "passive"))
      (node (ref "T52") (pin "1") (pinfunction "B_1") (pintype "passive"))
    )
    (net (code "69") (name "/5B3") (class "Default")
      (node (ref "RN61") (pin "6") (pinfunction "6_6") (pintype "passive"))
      (node (ref "T53") (pin "1") (pinfunction "B_1") (pintype "passive"))
    )
    (net (code "70") (name "/5B4") (class "Default")
      (node (ref "RN61") (pin "7") (pinfunction "7_7") (pintype "passive"))
      (node (ref "T54") (pin "1") (pinfunction "B_1") (pintype "passive"))
    )
    (net (code "71") (name "/5B5") (class "Default")
      (node (ref "RN61") (pin "8") (pinfunction "8_8") (pintype "passive"))
      (node (ref "T55") (pin "1") (pinfunction "B_1") (pintype "passive"))
    )
    (net (code "72") (name "/5B6") (class "Default")
      (node (ref "RN70") (pin "5") (pinfunction "5_5") (pintype "passive"))
      (node (ref "T56") (pin "1") (pinfunction "B_1") (pintype "passive"))
    )
    (net (code "73") (name "/5B7") (class "Default")
      (node (ref "RN70") (pin "6") (pinfunction "6_6") (pintype "passive"))
      (node (ref "T57") (pin "1") (pinfunction "B_1") (pintype "passive"))
    )
    (net (code "74") (name "/5B8") (class "Default")
      (node (ref "RN70") (pin "7") (pinfunction "7_7") (pintype "passive"))
      (node (ref "T58") (pin "1") (pinfunction "B_1") (pintype "passive"))
    )
    (net (code "75") (name "/5B9") (class "Default")
      (node (ref "RN70") (pin "8") (pinfunction "8_8") (pintype "passive"))
      (node (ref "T59") (pin "1") (pinfunction "B_1") (pintype "passive"))
    )
    (net (code "76") (name "/5C") (class "Default")
      (node (ref "IC5") (pin "2") (pinfunction "QC_2") (pintype "tri_state"))
      (node (ref "RN50") (pin "2") (pinfunction "2_2") (pintype "passive"))
    )
    (net (code "77") (name "/5D") (class "Default")
      (node (ref "IC5") (pin "3") (pinfunction "QD_3") (pintype "tri_state"))
      (node (ref "RN50") (pin "1") (pinfunction "1_1") (pintype "passive"))
    )
    (net (code "78") (name "/5E") (class "Default")
      (node (ref "IC5") (pin "4") (pinfunction "QE_4") (pintype "tri_state"))
      (node (ref "RN51") (pin "4") (pinfunction "4_4") (pintype "passive"))
    )
    (net (code "79") (name "/5F") (class "Default")
      (node (ref "IC5") (pin "5") (pinfunction "QF_5") (pintype "tri_state"))
      (node (ref "RN51") (pin "3") (pinfunction "3_3") (pintype "passive"))
    )
    (net (code "80") (name "/5G") (class "Default")
      (node (ref "IC5") (pin "6") (pinfunction "QG_6") (pintype "tri_state"))
      (node (ref "RN51") (pin "2") (pinfunction "2_2") (pintype "passive"))
    )
    (net (code "81") (name "/5H") (class "Default")
      (node (ref "IC5") (pin "7") (pinfunction "QH_7") (pintype "tri_state"))
      (node (ref "RN51") (pin "1") (pinfunction "1_1") (pintype "passive"))
    )
    (net (code "82") (name "/6A") (class "Default")
      (node (ref "IC6") (pin "15") (pinfunction "QA_15") (pintype "tri_state"))
      (node (ref "RN60") (pin "4") (pinfunction "4_4") (pintype "passive"))
    )
    (net (code "83") (name "/6B") (class "Default")
      (node (ref "IC6") (pin "1") (pinfunction "QB_1") (pintype "tri_state"))
      (node (ref "RN60") (pin "3") (pinfunction "3_3") (pintype "passive"))
    )
    (net (code "84") (name "/6B0") (class "Default")
      (node (ref "RN81") (pin "7") (pinfunction "7_7") (pintype "passive"))
      (node (ref "T60") (pin "1") (pinfunction "B_1") (pintype "passive"))
    )
    (net (code "85") (name "/6B1") (class "Default")
      (node (ref "RN81") (pin "8") (pinfunction "8_8") (pintype "passive"))
      (node (ref "T61") (pin "1") (pinfunction "B_1") (pintype "passive"))
    )
    (net (code "86") (name "/6B2") (class "Default")
      (node (ref "RN71") (pin "7") (pinfunction "7_7") (pintype "passive"))
      (node (ref "T62") (pin "1") (pinfunction "B_1") (pintype "passive"))
    )
    (net (code "87") (name "/6B3") (class "Default")
      (node (ref "RN71") (pin "8") (pinfunction "8_8") (pintype "passive"))
      (node (ref "T63") (pin "1") (pinfunction "B_1") (pintype "passive"))
    )
    (net (code "88") (name "/6B4") (class "Default")
      (node (ref "RN80") (pin "5") (pinfunction "5_5") (pintype "passive"))
      (node (ref "T64") (pin "1") (pinfunction "B_1") (pintype "passive"))
    )
    (net (code "89") (name "/6B5") (class "Default")
      (node (ref "RN80") (pin "6") (pinfunction "6_6") (pintype "passive"))
      (node (ref "T65") (pin "1") (pinfunction "B_1") (pintype "passive"))
    )
    (net (code "90") (name "/6B6") (class "Default")
      (node (ref "RN80") (pin "7") (pinfunction "7_7") (pintype "passive"))
      (node (ref "T66") (pin "1") (pinfunction "B_1") (pintype "passive"))
    )
    (net (code "91") (name "/6B7") (class "Default")
      (node (ref "RN80") (pin "8") (pinfunction "8_8") (pintype "passive"))
      (node (ref "T67") (pin "1") (pinfunction "B_1") (pintype "passive"))
    )
    (net (code "92") (name "/6B8") (class "Default")
      (node (ref "RN81") (pin "5") (pinfunction "5_5") (pintype "passive"))
      (node (ref "T68") (pin "1") (pinfunction "B_1") (pintype "passive"))
    )
    (net (code "93") (name "/6B9") (class "Default")
      (node (ref "RN81") (pin "6") (pinfunction "6_6") (pintype "passive"))
      (node (ref "T69") (pin "1") (pinfunction "B_1") (pintype "passive"))
    )
    (net (code "94") (name "/6C") (class "Default")
      (node (ref "IC6") (pin "2") (pinfunction "QC_2") (pintype "tri_state"))
      (node (ref "RN60") (pin "2") (pinfunction "2_2") (pintype "passive"))
    )
    (net (code "95") (name "/6D") (class "Default")
      (node (ref "IC6") (pin "3") (pinfunction "QD_3") (pintype "tri_state"))
      (node (ref "RN60") (pin "1") (pinfunction "1_1") (pintype "passive"))
    )
    (net (code "96") (name "/6E") (class "Default")
      (node (ref "IC6") (pin "4") (pinfunction "QE_4") (pintype "tri_state"))
      (node (ref "RN61") (pin "4") (pinfunction "4_4") (pintype "passive"))
    )
    (net (code "97") (name "/6F") (class "Default")
      (node (ref "IC6") (pin "5") (pinfunction "QF_5") (pintype "tri_state"))
      (node (ref "RN61") (pin "3") (pinfunction "3_3") (pintype "passive"))
    )
    (net (code "98") (name "/6G") (class "Default")
      (node (ref "IC6") (pin "6") (pinfunction "QG_6") (pintype "tri_state"))
      (node (ref "RN61") (pin "2") (pinfunction "2_2") (pintype "passive"))
    )
    (net (code "99") (name "/6H") (class "Default")
      (node (ref "IC6") (pin "7") (pinfunction "QH_7") (pintype "tri_state"))
      (node (ref "RN61") (pin "1") (pinfunction "1_1") (pintype "passive"))
    )
    (net (code "100") (name "/7A") (class "Default")
      (node (ref "IC7") (pin "15") (pinfunction "QA_15") (pintype "tri_state"))
      (node (ref "RN70") (pin "4") (pinfunction "4_4") (pintype "passive"))
    )
    (net (code "101") (name "/7B") (class "Default")
      (node (ref "IC7") (pin "1") (pinfunction "QB_1") (pintype "tri_state"))
      (node (ref "RN70") (pin "3") (pinfunction "3_3") (pintype "passive"))
    )
    (net (code "102") (name "/7C") (class "Default")
      (node (ref "IC7") (pin "2") (pinfunction "QC_2") (pintype "tri_state"))
      (node (ref "RN70") (pin "2") (pinfunction "2_2") (pintype "passive"))
    )
    (net (code "103") (name "/7D") (class "Default")
      (node (ref "IC7") (pin "3") (pinfunction "QD_3") (pintype "tri_state"))
      (node (ref "RN70") (pin "1") (pinfunction "1_1") (pintype "passive"))
    )
    (net (code "104") (name "/7E") (class "Default")
      (node (ref "IC7") (pin "4") (pinfunction "QE_4") (pintype "tri_state"))
      (node (ref "RN71") (pin "4") (pinfunction "4_4") (pintype "passive"))
    )
    (net (code "105") (name "/7F") (class "Default")
      (node (ref "IC7") (pin "5") (pinfunction "QF_5") (pintype "tri_state"))
      (node (ref "RN71") (pin "3") (pinfunction "3_3") (pintype "passive"))
    )
    (net (code "106") (name "/7G") (class "Default")
      (node (ref "IC7") (pin "6") (pinfunction "QG_6") (pintype "tri_state"))
      (node (ref "RN71") (pin "2") (pinfunction "2_2") (pintype "passive"))
    )
    (net (code "107") (name "/7H") (class "Default")
      (node (ref "IC7") (pin "7") (pinfunction "QH_7") (pintype "tri_state"))
      (node (ref "RN71") (pin "1") (pinfunction "1_1") (pintype "passive"))
    )
    (net (code "108") (name "/8A") (class "Default")
      (node (ref "IC8") (pin "15") (pinfunction "QA_15") (pintype "tri_state"))
      (node (ref "RN80") (pin "4") (pinfunction "4_4") (pintype "passive"))
    )
    (net (code "109") (name "/8B") (class "Default")
      (node (ref "IC8") (pin "1") (pinfunction "QB_1") (pintype "tri_state"))
      (node (ref "RN80") (pin "3") (pinfunction "3_3") (pintype "passive"))
    )
    (net (code "110") (name "/8C") (class "Default")
      (node (ref "IC8") (pin "2") (pinfunction "QC_2") (pintype "tri_state"))
      (node (ref "RN80") (pin "2") (pinfunction "2_2") (pintype "passive"))
    )
    (net (code "111") (name "/8D") (class "Default")
      (node (ref "IC8") (pin "3") (pinfunction "QD_3") (pintype "tri_state"))
      (node (ref "RN80") (pin "1") (pinfunction "1_1") (pintype "passive"))
    )
    (net (code "112") (name "/8E") (class "Default")
      (node (ref "IC8") (pin "4") (pinfunction "QE_4") (pintype "tri_state"))
      (node (ref "RN81") (pin "4") (pinfunction "4_4") (pintype "passive"))
    )
    (net (code "113") (name "/8F") (class "Default")
      (node (ref "IC8") (pin "5") (pinfunction "QF_5") (pintype "tri_state"))
      (node (ref "RN81") (pin "3") (pinfunction "3_3") (pintype "passive"))
    )
    (net (code "114") (name "/8G") (class "Default")
      (node (ref "IC8") (pin "6") (pinfunction "QG_6") (pintype "tri_state"))
      (node (ref "RN81") (pin "2") (pinfunction "2_2") (pintype "passive"))
    )
    (net (code "115") (name "/8H") (class "Default")
      (node (ref "IC8") (pin "7") (pinfunction "QH_7") (pintype "tri_state"))
      (node (ref "RN81") (pin "1") (pinfunction "1_1") (pintype "passive"))
    )
    (net (code "116") (name "/EN") (class "Default")
      (node (ref "IC1") (pin "13") (pinfunction "G_13") (pintype "input"))
      (node (ref "IC2") (pin "13") (pinfunction "G_13") (pintype "input"))
      (node (ref "IC3") (pin "13") (pinfunction "G_13") (pintype "input"))
      (node (ref "IC4") (pin "13") (pinfunction "G_13") (pintype "input"))
      (node (ref "IC5") (pin "13") (pinfunction "G_13") (pintype "input"))
      (node (ref "IC6") (pin "13") (pinfunction "G_13") (pintype "input"))
      (node (ref "IC7") (pin "13") (pinfunction "G_13") (pintype "input"))
      (node (ref "IC8") (pin "13") (pinfunction "G_13") (pintype "input"))
      (node (ref "JP1") (pin "1") (pinfunction "1_1") (pintype "passive"))
    )
    (net (code "117") (name "/GL1") (class "Default")
      (node (ref "RN31") (pin "5") (pinfunction "5_5") (pintype "passive"))
      (node (ref "T1") (pin "1") (pinfunction "B_1") (pintype "passive"))
    )
    (net (code "118") (name "/GL2") (class "Default")
      (node (ref "RN31") (pin "6") (pinfunction "6_6") (pintype "passive"))
      (node (ref "T2") (pin "1") (pinfunction "B_1") (pintype "passive"))
    )
    (net (code "119") (name "/GL3") (class "Default")
      (node (ref "RN60") (pin "7") (pinfunction "7_7") (pintype "passive"))
      (node (ref "T3") (pin "1") (pinfunction "B_1") (pintype "passive"))
    )
    (net (code "120") (name "/GL4") (class "Default")
      (node (ref "RN60") (pin "8") (pinfunction "8_8") (pintype "passive"))
      (node (ref "T4") (pin "1") (pinfunction "B_1") (pintype "passive"))
    )
    (net (code "121") (name "/MOSI") (class "Default")
      (node (ref "IC1") (pin "14") (pinfunction "SER_14") (pintype "input"))
      (node (ref "JP1") (pin "4") (pinfunction "4_4") (pintype "passive"))
    )
    (net (code "122") (name "/N1_B0") (class "Default")
      (node (ref "RN20") (pin "6") (pinfunction "6_6") (pintype "passive"))
      (node (ref "T11") (pin "1") (pinfunction "B_1") (pintype "passive"))
    )
    (net (code "123") (name "/N1_B1") (class "Default")
      (node (ref "RN10") (pin "5") (pinfunction "5_5") (pintype "passive"))
      (node (ref "T12") (pin "1") (pinfunction "B_1") (pintype "passive"))
    )
    (net (code "124") (name "/N1_B2") (class "Default")
      (node (ref "RN10") (pin "6") (pinfunction "6_6") (pintype "passive"))
      (node (ref "T13") (pin "1") (pinfunction "B_1") (pintype "passive"))
    )
    (net (code "125") (name "/N1_B3") (class "Default")
      (node (ref "RN10") (pin "7") (pinfunction "7_7") (pintype "passive"))
      (node (ref "T14") (pin "1") (pinfunction "B_1") (pintype "passive"))
    )
    (net (code "126") (name "/N1_B4") (class "Default")
      (node (ref "RN10") (pin "8") (pinfunction "8_8") (pintype "passive"))
      (node (ref "T15") (pin "1") (pinfunction "B_1") (pintype "passive"))
    )
    (net (code "127") (name "/N1_B5") (class "Default")
      (node (ref "RN11") (pin "5") (pinfunction "5_5") (pintype "passive"))
      (node (ref "T16") (pin "1") (pinfunction "B_1") (pintype "passive"))
    )
    (net (code "128") (name "/N1_B6") (class "Default")
      (node (ref "RN11") (pin "6") (pinfunction "6_6") (pintype "passive"))
      (node (ref "T17") (pin "1") (pinfunction "B_1") (pintype "passive"))
    )
    (net (code "129") (name "/N1_B7") (class "Default")
      (node (ref "RN11") (pin "7") (pinfunction "7_7") (pintype "passive"))
      (node (ref "T18") (pin "1") (pinfunction "B_1") (pintype "passive"))
    )
    (net (code "130") (name "/N1_B8") (class "Default")
      (node (ref "RN11") (pin "8") (pinfunction "8_8") (pintype "passive"))
      (node (ref "T19") (pin "1") (pinfunction "B_1") (pintype "passive"))
    )
    (net (code "131") (name "/N1_B9") (class "Default")
      (node (ref "RN20") (pin "5") (pinfunction "5_5") (pintype "passive"))
      (node (ref "T10") (pin "1") (pinfunction "B_1") (pintype "passive"))
    )
    (net (code "132") (name "/N1_K0") (class "Default")
      (node (ref "T12") (pin "3") (pinfunction "C_3") (pintype "passive"))
      (node (ref "U$4") (pin "P10") (pinfunction "0_P10") (pintype "bidirectional"))
    )
    (net (code "133") (name "/N1_K1") (class "Default")
      (node (ref "T11") (pin "3") (pinfunction "C_3") (pintype "passive"))
      (node (ref "U$4") (pin "P1") (pinfunction "1_P1") (pintype "bidirectional"))
    )
    (net (code "134") (name "/N1_K2") (class "Default")
      (node (ref "T10") (pin "3") (pinfunction "C_3") (pintype "passive"))
      (node (ref "U$4") (pin "P2") (pinfunction "2_P2") (pintype "bidirectional"))
    )
    (net (code "135") (name "/N1_K3") (class "Default")
      (node (ref "T19") (pin "3") (pinfunction "C_3") (pintype "passive"))
      (node (ref "U$4") (pin "P3") (pinfunction "3_P3") (pintype "bidirectional"))
    )
    (net (code "136") (name "/N1_K4") (class "Default")
      (node (ref "T18") (pin "3") (pinfunction "C_3") (pintype "passive"))
      (node (ref "U$4") (pin "P4") (pinfunction "4_P4") (pintype "bidirectional"))
    )
    (net (code "137") (name "/N1_K5") (class "Default")
      (node (ref "T17") (pin "3") (pinfunction "C_3") (pintype "passive"))
      (node (ref "U$4") (pin "P5") (pinfunction "5_P5") (pintype "bidirectional"))
    )
    (net (code "138") (name "/N1_K6") (class "Default")
      (node (ref "T16") (pin "3") (pinfunction "C_3") (pintype "passive"))
      (node (ref "U$4") (pin "P6") (pinfunction "6_P6") (pintype "bidirectional"))
    )
    (net (code "139") (name "/N1_K7") (class "Default")
      (node (ref "T15") (pin "3") (pinfunction "C_3") (pintype "passive"))
      (node (ref "U$4") (pin "P7") (pinfunction "7_P7") (pintype "bidirectional"))
    )
    (net (code "140") (name "/N1_K8") (class "Default")
      (node (ref "T14") (pin "3") (pinfunction "C_3") (pintype "passive"))
      (node (ref "U$4") (pin "P8") (pinfunction "8_P8") (pintype "bidirectional"))
    )
    (net (code "141") (name "/N1_K9") (class "Default")
      (node (ref "T13") (pin "3") (pinfunction "C_3") (pintype "passive"))
      (node (ref "U$4") (pin "P9") (pinfunction "9_P9") (pintype "bidirectional"))
    )
    (net (code "142") (name "/N2_0") (class "Default")
      (node (ref "T22") (pin "3") (pinfunction "C_3") (pintype "passive"))
      (node (ref "U$5") (pin "P10") (pinfunction "0_P10") (pintype "bidirectional"))
    )
    (net (code "143") (name "/N2_1") (class "Default")
      (node (ref "T21") (pin "3") (pinfunction "C_3") (pintype "passive"))
      (node (ref "U$5") (pin "P1") (pinfunction "1_P1") (pintype "bidirectional"))
    )
    (net (code "144") (name "/N2_2") (class "Default")
      (node (ref "T20") (pin "3") (pinfunction "C_3") (pintype "passive"))
      (node (ref "U$5") (pin "P2") (pinfunction "2_P2") (pintype "bidirectional"))
    )
    (net (code "145") (name "/N2_3") (class "Default")
      (node (ref "T29") (pin "3") (pinfunction "C_3") (pintype "passive"))
      (node (ref "U$5") (pin "P3") (pinfunction "3_P3") (pintype "bidirectional"))
    )
    (net (code "146") (name "/N2_4") (class "Default")
      (node (ref "T28") (pin "3") (pinfunction "C_3") (pintype "passive"))
      (node (ref "U$5") (pin "P4") (pinfunction "4_P4") (pintype "bidirectional"))
    )
    (net (code "147") (name "/N2_5") (class "Default")
      (node (ref "T27") (pin "3") (pinfunction "C_3") (pintype "passive"))
      (node (ref "U$5") (pin "P5") (pinfunction "5_P5") (pintype "bidirectional"))
    )
    (net (code "148") (name "/N2_6") (class "Default")
      (node (ref "T26") (pin "3") (pinfunction "C_3") (pintype "passive"))
      (node (ref "U$5") (pin "P6") (pinfunction "6_P6") (pintype "bidirectional"))
    )
    (net (code "149") (name "/N2_7") (class "Default")
      (node (ref "T25") (pin "3") (pinfunction "C_3") (pintype "passive"))
      (node (ref "U$5") (pin "P7") (pinfunction "7_P7") (pintype "bidirectional"))
    )
    (net (code "150") (name "/N2_8") (class "Default")
      (node (ref "T24") (pin "3") (pinfunction "C_3") (pintype "passive"))
      (node (ref "U$5") (pin "P8") (pinfunction "8_P8") (pintype "bidirectional"))
    )
    (net (code "151") (name "/N2_9") (class "Default")
      (node (ref "T23") (pin "3") (pinfunction "C_3") (pintype "passive"))
      (node (ref "U$5") (pin "P9") (pinfunction "9_P9") (pintype "bidirectional"))
    )
    (net (code "152") (name "/N3_0") (class "Default")
      (node (ref "T32") (pin "3") (pinfunction "C_3") (pintype "passive"))
      (node (ref "U$6") (pin "P10") (pinfunction "0_P10") (pintype "bidirectional"))
    )
    (net (code "153") (name "/N3_1") (class "Default")
      (node (ref "T31") (pin "3") (pinfunction "C_3") (pintype "passive"))
      (node (ref "U$6") (pin "P1") (pinfunction "1_P1") (pintype "bidirectional"))
    )
    (net (code "154") (name "/N3_2") (class "Default")
      (node (ref "T30") (pin "3") (pinfunction "C_3") (pintype "passive"))
      (node (ref "U$6") (pin "P2") (pinfunction "2_P2") (pintype "bidirectional"))
    )
    (net (code "155") (name "/N3_3") (class "Default")
      (node (ref "T39") (pin "3") (pinfunction "C_3") (pintype "passive"))
      (node (ref "U$6") (pin "P3") (pinfunction "3_P3") (pintype "bidirectional"))
    )
    (net (code "156") (name "/N3_4") (class "Default")
      (node (ref "T38") (pin "3") (pinfunction "C_3") (pintype "passive"))
      (node (ref "U$6") (pin "P4") (pinfunction "4_P4") (pintype "bidirectional"))
    )
    (net (code "157") (name "/N3_5") (class "Default")
      (node (ref "T37") (pin "3") (pinfunction "C_3") (pintype "passive"))
      (node (ref "U$6") (pin "P5") (pinfunction "5_P5") (pintype "bidirectional"))
    )
    (net (code "158") (name "/N3_6") (class "Default")
      (node (ref "T36") (pin "3") (pinfunction "C_3") (pintype "passive"))
      (node (ref "U$6") (pin "P6") (pinfunction "6_P6") (pintype "bidirectional"))
    )
    (net (code "159") (name "/N3_7") (class "Default")
      (node (ref "T35") (pin "3") (pinfunction "C_3") (pintype "passive"))
      (node (ref "U$6") (pin "P7") (pinfunction "7_P7") (pintype "bidirectional"))
    )
    (net (code "160") (name "/N3_8") (class "Default")
      (node (ref "T34") (pin "3") (pinfunction "C_3") (pintype "passive"))
      (node (ref "U$6") (pin "P8") (pinfunction "8_P8") (pintype "bidirectional"))
    )
    (net (code "161") (name "/N3_9") (class "Default")
      (node (ref "T33") (pin "3") (pinfunction "C_3") (pintype "passive"))
      (node (ref "U$6") (pin "P9") (pinfunction "9_P9") (pintype "bidirectional"))
    )
    (net (code "162") (name "/N4_0") (class "Default")
      (node (ref "T42") (pin "3") (pinfunction "C_3") (pintype "passive"))
      (node (ref "U$7") (pin "P10") (pinfunction "0_P10") (pintype "bidirectional"))
    )
    (net (code "163") (name "/N4_1") (class "Default")
      (node (ref "T41") (pin "3") (pinfunction "C_3") (pintype "passive"))
      (node (ref "U$7") (pin "P1") (pinfunction "1_P1") (pintype "bidirectional"))
    )
    (net (code "164") (name "/N4_2") (class "Default")
      (node (ref "T40") (pin "3") (pinfunction "C_3") (pintype "passive"))
      (node (ref "U$7") (pin "P2") (pinfunction "2_P2") (pintype "bidirectional"))
    )
    (net (code "165") (name "/N4_3") (class "Default")
      (node (ref "T49") (pin "3") (pinfunction "C_3") (pintype "passive"))
      (node (ref "U$7") (pin "P3") (pinfunction "3_P3") (pintype "bidirectional"))
    )
    (net (code "166") (name "/N4_4") (class "Default")
      (node (ref "T48") (pin "3") (pinfunction "C_3") (pintype "passive"))
      (node (ref "U$7") (pin "P4") (pinfunction "4_P4") (pintype "bidirectional"))
    )
    (net (code "167") (name "/N4_5") (class "Default")
      (node (ref "T47") (pin "3") (pinfunction "C_3") (pintype "passive"))
      (node (ref "U$7") (pin "P5") (pinfunction "5_P5") (pintype "bidirectional"))
    )
    (net (code "168") (name "/N4_6") (class "Default")
      (node (ref "T46") (pin "3") (pinfunction "C_3") (pintype "passive"))
      (node (ref "U$7") (pin "P6") (pinfunction "6_P6") (pintype "bidirectional"))
    )
    (net (code "169") (name "/N4_7") (class "Default")
      (node (ref "T45") (pin "3") (pinfunction "C_3") (pintype "passive"))
      (node (ref "U$7") (pin "P7") (pinfunction "7_P7") (pintype "bidirectional"))
    )
    (net (code "170") (name "/N4_8") (class "Default")
      (node (ref "T44") (pin "3") (pinfunction "C_3") (pintype "passive"))
      (node (ref "U$7") (pin "P8") (pinfunction "8_P8") (pintype "bidirectional"))
    )
    (net (code "171") (name "/N4_9") (class "Default")
      (node (ref "T43") (pin "3") (pinfunction "C_3") (pintype "passive"))
      (node (ref "U$7") (pin "P9") (pinfunction "9_P9") (pintype "bidirectional"))
    )
    (net (code "172") (name "/N5_0") (class "Default")
      (node (ref "T52") (pin "3") (pinfunction "C_3") (pintype "passive"))
      (node (ref "U$8") (pin "P10") (pinfunction "0_P10") (pintype "bidirectional"))
    )
    (net (code "173") (name "/N5_1") (class "Default")
      (node (ref "T51") (pin "3") (pinfunction "C_3") (pintype "passive"))
      (node (ref "U$8") (pin "P1") (pinfunction "1_P1") (pintype "bidirectional"))
    )
    (net (code "174") (name "/N5_2") (class "Default")
      (node (ref "T50") (pin "3") (pinfunction "C_3") (pintype "passive"))
      (node (ref "U$8") (pin "P2") (pinfunction "2_P2") (pintype "bidirectional"))
    )
    (net (code "175") (name "/N5_3") (class "Default")
      (node (ref "T59") (pin "3") (pinfunction "C_3") (pintype "passive"))
      (node (ref "U$8") (pin "P3") (pinfunction "3_P3") (pintype "bidirectional"))
    )
    (net (code "176") (name "/N5_4") (class "Default")
      (node (ref "T58") (pin "3") (pinfunction "C_3") (pintype "passive"))
      (node (ref "U$8") (pin "P4") (pinfunction "4_P4") (pintype "bidirectional"))
    )
    (net (code "177") (name "/N5_5") (class "Default")
      (node (ref "T57") (pin "3") (pinfunction "C_3") (pintype "passive"))
      (node (ref "U$8") (pin "P5") (pinfunction "5_P5") (pintype "bidirectional"))
    )
    (net (code "178") (name "/N5_6") (class "Default")
      (node (ref "T56") (pin "3") (pinfunction "C_3") (pintype "passive"))
      (node (ref "U$8") (pin "P6") (pinfunction "6_P6") (pintype "bidirectional"))
    )
    (net (code "179") (name "/N5_7") (class "Default")
      (node (ref "T55") (pin "3") (pinfunction "C_3") (pintype "passive"))
      (node (ref "U$8") (pin "P7") (pinfunction "7_P7") (pintype "bidirectional"))
    )
    (net (code "180") (name "/N5_8") (class "Default")
      (node (ref "T54") (pin "3") (pinfunction "C_3") (pintype "passive"))
      (node (ref "U$8") (pin "P8") (pinfunction "8_P8") (pintype "bidirectional"))
    )
    (net (code "181") (name "/N5_9") (class "Default")
      (node (ref "T53") (pin "3") (pinfunction "C_3") (pintype "passive"))
      (node (ref "U$8") (pin "P9") (pinfunction "9_P9") (pintype "bidirectional"))
    )
    (net (code "182") (name "/N6_0") (class "Default")
      (node (ref "T62") (pin "3") (pinfunction "C_3") (pintype "passive"))
      (node (ref "U$9") (pin "P10") (pinfunction "0_P10") (pintype "bidirectional"))
    )
    (net (code "183") (name "/N6_1") (class "Default")
      (node (ref "T61") (pin "3") (pinfunction "C_3") (pintype "passive"))
      (node (ref "U$9") (pin "P1") (pinfunction "1_P1") (pintype "bidirectional"))
    )
    (net (code "184") (name "/N6_2") (class "Default")
      (node (ref "T60") (pin "3") (pinfunction "C_3") (pintype "passive"))
      (node (ref "U$9") (pin "P2") (pinfunction "2_P2") (pintype "bidirectional"))
    )
    (net (code "185") (name "/N6_3") (class "Default")
      (node (ref "T69") (pin "3") (pinfunction "C_3") (pintype "passive"))
      (node (ref "U$9") (pin "P3") (pinfunction "3_P3") (pintype "bidirectional"))
    )
    (net (code "186") (name "/N6_4") (class "Default")
      (node (ref "T68") (pin "3") (pinfunction "C_3") (pintype "passive"))
      (node (ref "U$9") (pin "P4") (pinfunction "4_P4") (pintype "bidirectional"))
    )
    (net (code "187") (name "/N6_5") (class "Default")
      (node (ref "T67") (pin "3") (pinfunction "C_3") (pintype "passive"))
      (node (ref "U$9") (pin "P5") (pinfunction "5_P5") (pintype "bidirectional"))
    )
    (net (code "188") (name "/N6_6") (class "Default")
      (node (ref "T66") (pin "3") (pinfunction "C_3") (pintype "passive"))
      (node (ref "U$9") (pin "P6") (pinfunction "6_P6") (pintype "bidirectional"))
    )
    (net (code "189") (name "/N6_7") (class "Default")
      (node (ref "T65") (pin "3") (pinfunction "C_3") (pintype "passive"))
      (node (ref "U$9") (pin "P7") (pinfunction "7_P7") (pintype "bidirectional"))
    )
    (net (code "190") (name "/N6_8") (class "Default")
      (node (ref "T64") (pin "3") (pinfunction "C_3") (pintype "passive"))
      (node (ref "U$9") (pin "P8") (pinfunction "8_P8") (pintype "bidirectional"))
    )
    (net (code "191") (name "/N6_9") (class "Default")
      (node (ref "T63") (pin "3") (pinfunction "C_3") (pintype "passive"))
      (node (ref "U$9") (pin "P9") (pinfunction "9_P9") (pintype "bidirectional"))
    )
    (net (code "192") (name "/RCK") (class "Default")
      (node (ref "IC1") (pin "12") (pinfunction "RCK_12") (pintype "input"))
      (node (ref "IC2") (pin "12") (pinfunction "RCK_12") (pintype "input"))
      (node (ref "IC3") (pin "12") (pinfunction "RCK_12") (pintype "input"))
      (node (ref "IC4") (pin "12") (pinfunction "RCK_12") (pintype "input"))
      (node (ref "IC5") (pin "12") (pinfunction "RCK_12") (pintype "input"))
      (node (ref "IC6") (pin "12") (pinfunction "RCK_12") (pintype "input"))
      (node (ref "IC7") (pin "12") (pinfunction "RCK_12") (pintype "input"))
      (node (ref "IC8") (pin "12") (pinfunction "RCK_12") (pintype "input"))
      (node (ref "JP1") (pin "5") (pinfunction "5_5") (pintype "passive"))
    )
    (net (code "193") (name "/SCK") (class "Default")
      (node (ref "IC1") (pin "11") (pinfunction "SCK_11") (pintype "input"))
      (node (ref "IC2") (pin "11") (pinfunction "SCK_11") (pintype "input"))
      (node (ref "IC3") (pin "11") (pinfunction "SCK_11") (pintype "input"))
      (node (ref "IC4") (pin "11") (pinfunction "SCK_11") (pintype "input"))
      (node (ref "IC5") (pin "11") (pinfunction "SCK_11") (pintype "input"))
      (node (ref "IC6") (pin "11") (pinfunction "SCK_11") (pintype "input"))
      (node (ref "IC7") (pin "11") (pinfunction "SCK_11") (pintype "input"))
      (node (ref "IC8") (pin "11") (pinfunction "SCK_11") (pintype "input"))
      (node (ref "JP1") (pin "3") (pinfunction "3_3") (pintype "passive"))
    )
    (net (code "194") (name "/SCL") (class "Default")
      (node (ref "IC1") (pin "10") (pinfunction "SCL_10") (pintype "input"))
      (node (ref "IC2") (pin "10") (pinfunction "SCL_10") (pintype "input"))
      (node (ref "IC3") (pin "10") (pinfunction "SCL_10") (pintype "input"))
      (node (ref "IC4") (pin "10") (pinfunction "SCL_10") (pintype "input"))
      (node (ref "IC5") (pin "10") (pinfunction "SCL_10") (pintype "input"))
      (node (ref "IC6") (pin "10") (pinfunction "SCL_10") (pintype "input"))
      (node (ref "IC7") (pin "10") (pinfunction "SCL_10") (pintype "input"))
      (node (ref "IC8") (pin "10") (pinfunction "SCL_10") (pintype "input"))
      (node (ref "JP1") (pin "2") (pinfunction "2_2") (pintype "passive"))
    )
    (net (code "195") (name "GND") (class "Default")
      (node (ref "C1") (pin "2") (pinfunction "2_2") (pintype "passive"))
      (node (ref "C2") (pin "2") (pinfunction "2_2") (pintype "passive"))
      (node (ref "C3") (pin "2") (pinfunction "2_2") (pintype "passive"))
      (node (ref "C4") (pin "2") (pinfunction "2_2") (pintype "passive"))
      (node (ref "C5") (pin "2") (pinfunction "2_2") (pintype "passive"))
      (node (ref "C6") (pin "2") (pinfunction "2_2") (pintype "passive"))
      (node (ref "C7") (pin "2") (pinfunction "2_2") (pintype "passive"))
      (node (ref "C8") (pin "2") (pinfunction "2_2") (pintype "passive"))
      (node (ref "IC1") (pin "8") (pinfunction "GND_8") (pintype "power_in"))
      (node (ref "IC2") (pin "8") (pinfunction "GND_8") (pintype "power_in"))
      (node (ref "IC3") (pin "8") (pinfunction "GND_8") (pintype "power_in"))
      (node (ref "IC4") (pin "8") (pinfunction "GND_8") (pintype "power_in"))
      (node (ref "IC5") (pin "8") (pinfunction "GND_8") (pintype "power_in"))
      (node (ref "IC6") (pin "8") (pinfunction "GND_8") (pintype "power_in"))
      (node (ref "IC7") (pin "8") (pinfunction "GND_8") (pintype "power_in"))
      (node (ref "IC8") (pin "8") (pinfunction "GND_8") (pintype "power_in"))
      (node (ref "JP1") (pin "6") (pinfunction "6_6") (pintype "passive"))
      (node (ref "JP2") (pin "2") (pinfunction "2_2") (pintype "passive"))
      (node (ref "JP2") (pin "3") (pinfunction "3_3") (pintype "passive"))
      (node (ref "JP2") (pin "4") (pinfunction "4_4") (pintype "passive"))
      (node (ref "JP2") (pin "5") (pinfunction "5_5") (pintype "passive"))
      (node (ref "T1") (pin "2") (pinfunction "E_2") (pintype "passive"))
      (node (ref "T10") (pin "2") (pinfunction "E_2") (pintype "passive"))
      (node (ref "T11") (pin "2") (pinfunction "E_2") (pintype "passive"))
      (node (ref "T12") (pin "2") (pinfunction "E_2") (pintype "passive"))
      (node (ref "T13") (pin "2") (pinfunction "E_2") (pintype "passive"))
      (node (ref "T14") (pin "2") (pinfunction "E_2") (pintype "passive"))
      (node (ref "T15") (pin "2") (pinfunction "E_2") (pintype "passive"))
      (node (ref "T16") (pin "2") (pinfunction "E_2") (pintype "passive"))
      (node (ref "T17") (pin "2") (pinfunction "E_2") (pintype "passive"))
      (node (ref "T18") (pin "2") (pinfunction "E_2") (pintype "passive"))
      (node (ref "T19") (pin "2") (pinfunction "E_2") (pintype "passive"))
      (node (ref "T2") (pin "2") (pinfunction "E_2") (pintype "passive"))
      (node (ref "T20") (pin "2") (pinfunction "E_2") (pintype "passive"))
      (node (ref "T21") (pin "2") (pinfunction "E_2") (pintype "passive"))
      (node (ref "T22") (pin "2") (pinfunction "E_2") (pintype "passive"))
      (node (ref "T23") (pin "2") (pinfunction "E_2") (pintype "passive"))
      (node (ref "T24") (pin "2") (pinfunction "E_2") (pintype "passive"))
      (node (ref "T25") (pin "2") (pinfunction "E_2") (pintype "passive"))
      (node (ref "T26") (pin "2") (pinfunction "E_2") (pintype "passive"))
      (node (ref "T27") (pin "2") (pinfunction "E_2") (pintype "passive"))
      (node (ref "T28") (pin "2") (pinfunction "E_2") (pintype "passive"))
      (node (ref "T29") (pin "2") (pinfunction "E_2") (pintype "passive"))
      (node (ref "T3") (pin "2") (pinfunction "E_2") (pintype "passive"))
      (node (ref "T30") (pin "2") (pinfunction "E_2") (pintype "passive"))
      (node (ref "T31") (pin "2") (pinfunction "E_2") (pintype "passive"))
      (node (ref "T32") (pin "2") (pinfunction "E_2") (pintype "passive"))
      (node (ref "T33") (pin "2") (pinfunction "E_2") (pintype "passive"))
      (node (ref "T34") (pin "2") (pinfunction "E_2") (pintype "passive"))
      (node (ref "T35") (pin "2") (pinfunction "E_2") (pintype "passive"))
      (node (ref "T36") (pin "2") (pinfunction "E_2") (pintype "passive"))
      (node (ref "T37") (pin "2") (pinfunction "E_2") (pintype "passive"))
      (node (ref "T38") (pin "2") (pinfunction "E_2") (pintype "passive"))
      (node (ref "T39") (pin "2") (pinfunction "E_2") (pintype "passive"))
      (node (ref "T4") (pin "2") (pinfunction "E_2") (pintype "passive"))
      (node (ref "T40") (pin "2") (pinfunction "E_2") (pintype "passive"))
      (node (ref "T41") (pin "2") (pinfunction "E_2") (pintype "passive"))
      (node (ref "T42") (pin "2") (pinfunction "E_2") (pintype "passive"))
      (node (ref "T43") (pin "2") (pinfunction "E_2") (pintype "passive"))
      (node (ref "T44") (pin "2") (pinfunction "E_2") (pintype "passive"))
      (node (ref "T45") (pin "2") (pinfunction "E_2") (pintype "passive"))
      (node (ref "T46") (pin "2") (pinfunction "E_2") (pintype "passive"))
      (node (ref "T47") (pin "2") (pinfunction "E_2") (pintype "passive"))
      (node (ref "T48") (pin "2") (pinfunction "E_2") (pintype "passive"))
      (node (ref "T49") (pin "2") (pinfunction "E_2") (pintype "passive"))
      (node (ref "T50") (pin "2") (pinfunction "E_2") (pintype "passive"))
      (node (ref "T51") (pin "2") (pinfunction "E_2") (pintype "passive"))
      (node (ref "T52") (pin "2") (pinfunction "E_2") (pintype "passive"))
      (node (ref "T53") (pin "2") (pinfunction "E_2") (pintype "passive"))
      (node (ref "T54") (pin "2") (pinfunction "E_2") (pintype "passive"))
      (node (ref "T55") (pin "2") (pinfunction "E_2") (pintype "passive"))
      (node (ref "T56") (pin "2") (pinfunction "E_2") (pintype "passive"))
      (node (ref "T57") (pin "2") (pinfunction "E_2") (pintype "passive"))
      (node (ref "T58") (pin "2") (pinfunction "E_2") (pintype "passive"))
      (node (ref "T59") (pin "2") (pinfunction "E_2") (pintype "passive"))
      (node (ref "T60") (pin "2") (pinfunction "E_2") (pintype "passive"))
      (node (ref "T61") (pin "2") (pinfunction "E_2") (pintype "passive"))
      (node (ref "T62") (pin "2") (pinfunction "E_2") (pintype "passive"))
      (node (ref "T63") (pin "2") (pinfunction "E_2") (pintype "passive"))
      (node (ref "T64") (pin "2") (pinfunction "E_2") (pintype "passive"))
      (node (ref "T65") (pin "2") (pinfunction "E_2") (pintype "passive"))
      (node (ref "T66") (pin "2") (pinfunction "E_2") (pintype "passive"))
      (node (ref "T67") (pin "2") (pinfunction "E_2") (pintype "passive"))
      (node (ref "T68") (pin "2") (pinfunction "E_2") (pintype "passive"))
      (node (ref "T69") (pin "2") (pinfunction "E_2") (pintype "passive"))
    )
    (net (code "196") (name "Net-(GL1-A)") (class "Default")
      (node (ref "GL1") (pin "1") (pinfunction "A_1") (pintype "passive"))
      (node (ref "R1") (pin "1") (pinfunction "1_1") (pintype "passive"))
    )
    (net (code "197") (name "Net-(GL1-A1)") (class "Default")
      (node (ref "GL1") (pin "2") (pinfunction "A1_2") (pintype "passive"))
      (node (ref "T1") (pin "3") (pinfunction "C_3") (pintype "passive"))
    )
    (net (code "198") (name "Net-(GL2-A)") (class "Default")
      (node (ref "GL2") (pin "1") (pinfunction "A_1") (pintype "passive"))
      (node (ref "R2") (pin "1") (pinfunction "1_1") (pintype "passive"))
    )
    (net (code "199") (name "Net-(GL2-A1)") (class "Default")
      (node (ref "GL2") (pin "2") (pinfunction "A1_2") (pintype "passive"))
      (node (ref "T2") (pin "3") (pinfunction "C_3") (pintype "passive"))
    )
    (net (code "200") (name "Net-(GL3-A)") (class "Default")
      (node (ref "GL3") (pin "1") (pinfunction "A_1") (pintype "passive"))
      (node (ref "R3") (pin "1") (pinfunction "1_1") (pintype "passive"))
    )
    (net (code "201") (name "Net-(GL3-A1)") (class "Default")
      (node (ref "GL3") (pin "2") (pinfunction "A1_2") (pintype "passive"))
      (node (ref "T3") (pin "3") (pinfunction "C_3") (pintype "passive"))
    )
    (net (code "202") (name "Net-(GL4-A)") (class "Default")
      (node (ref "GL4") (pin "1") (pinfunction "A_1") (pintype "passive"))
      (node (ref "R4") (pin "1") (pinfunction "1_1") (pintype "passive"))
    )
    (net (code "203") (name "Net-(GL4-A1)") (class "Default")
      (node (ref "GL4") (pin "2") (pinfunction "A1_2") (pintype "passive"))
      (node (ref "T4") (pin "3") (pinfunction "C_3") (pintype "passive"))
    )
    (net (code "204") (name "Net-(IC1A-QH*)") (class "Default")
      (node (ref "IC1") (pin "9") (pinfunction "QH*_9") (pintype "tri_state"))
      (node (ref "IC2") (pin "14") (pinfunction "SER_14") (pintype "input"))
    )
    (net (code "205") (name "Net-(IC2A-QH*)") (class "Default")
      (node (ref "IC2") (pin "9") (pinfunction "QH*_9") (pintype "tri_state"))
      (node (ref "IC3") (pin "14") (pinfunction "SER_14") (pintype "input"))
    )
    (net (code "206") (name "Net-(IC3A-QH*)") (class "Default")
      (node (ref "IC3") (pin "9") (pinfunction "QH*_9") (pintype "tri_state"))
      (node (ref "IC4") (pin "14") (pinfunction "SER_14") (pintype "input"))
    )
    (net (code "207") (name "Net-(IC4A-QH*)") (class "Default")
      (node (ref "IC4") (pin "9") (pinfunction "QH*_9") (pintype "tri_state"))
      (node (ref "IC5") (pin "14") (pinfunction "SER_14") (pintype "input"))
    )
    (net (code "208") (name "Net-(IC5A-QH*)") (class "Default")
      (node (ref "IC5") (pin "9") (pinfunction "QH*_9") (pintype "tri_state"))
      (node (ref "IC6") (pin "14") (pinfunction "SER_14") (pintype "input"))
    )
    (net (code "209") (name "Net-(IC6A-QH*)") (class "Default")
      (node (ref "IC6") (pin "9") (pinfunction "QH*_9") (pintype "tri_state"))
      (node (ref "IC7") (pin "14") (pinfunction "SER_14") (pintype "input"))
    )
    (net (code "210") (name "Net-(IC7A-QH*)") (class "Default")
      (node (ref "IC7") (pin "9") (pinfunction "QH*_9") (pintype "tri_state"))
      (node (ref "IC8") (pin "14") (pinfunction "SER_14") (pintype "input"))
    )
    (net (code "211") (name "Net-(U$4-A)") (class "Default")
      (node (ref "R10") (pin "1") (pinfunction "1_1") (pintype "passive"))
      (node (ref "U$4") (pin "P11") (pinfunction "A_P11") (pintype "bidirectional"))
    )
    (net (code "212") (name "Net-(U$5-A)") (class "Default")
      (node (ref "R20") (pin "1") (pinfunction "1_1") (pintype "passive"))
      (node (ref "U$5") (pin "P11") (pinfunction "A_P11") (pintype "bidirectional"))
    )
    (net (code "213") (name "Net-(U$6-A)") (class "Default")
      (node (ref "R30") (pin "1") (pinfunction "1_1") (pintype "passive"))
      (node (ref "U$6") (pin "P11") (pinfunction "A_P11") (pintype "bidirectional"))
    )
    (net (code "214") (name "Net-(U$7-A)") (class "Default")
      (node (ref "R40") (pin "1") (pinfunction "1_1") (pintype "passive"))
      (node (ref "U$7") (pin "P11") (pinfunction "A_P11") (pintype "bidirectional"))
    )
    (net (code "215") (name "Net-(U$8-A)") (class "Default")
      (node (ref "R50") (pin "1") (pinfunction "1_1") (pintype "passive"))
      (node (ref "U$8") (pin "P11") (pinfunction "A_P11") (pintype "bidirectional"))
    )
    (net (code "216") (name "Net-(U$9-A)") (class "Default")
      (node (ref "R60") (pin "1") (pinfunction "1_1") (pintype "passive"))
      (node (ref "U$9") (pin "P11") (pinfunction "A_P11") (pintype "bidirectional"))
    )
    (net (code "217") (name "VDD") (class "Default")
      (node (ref "JP2") (pin "1") (pinfunction "1_1") (pintype "passive"))
      (node (ref "R1") (pin "2") (pinfunction "2_2") (pintype "passive"))
      (node (ref "R10") (pin "2") (pinfunction "2_2") (pintype "passive"))
      (node (ref "R2") (pin "2") (pinfunction "2_2") (pintype "passive"))
      (node (ref "R20") (pin "2") (pinfunction "2_2") (pintype "passive"))
      (node (ref "R3") (pin "2") (pinfunction "2_2") (pintype "passive"))
      (node (ref "R30") (pin "2") (pinfunction "2_2") (pintype "passive"))
      (node (ref "R4") (pin "2") (pinfunction "2_2") (pintype "passive"))
      (node (ref "R40") (pin "2") (pinfunction "2_2") (pintype "passive"))
      (node (ref "R50") (pin "2") (pinfunction "2_2") (pintype "passive"))
      (node (ref "R60") (pin "2") (pinfunction "2_2") (pintype "passive"))
    )
    (net (code "218") (name "unconnected-(IC8A-QH*-Pad9)") (class "Default")
      (node (ref "IC8") (pin "9") (pinfunction "QH*_9") (pintype "tri_state"))
    )
  )
)
